# WAK-Pipe-v11.net
KiCad netlist of a schematic drawn in EAGLE
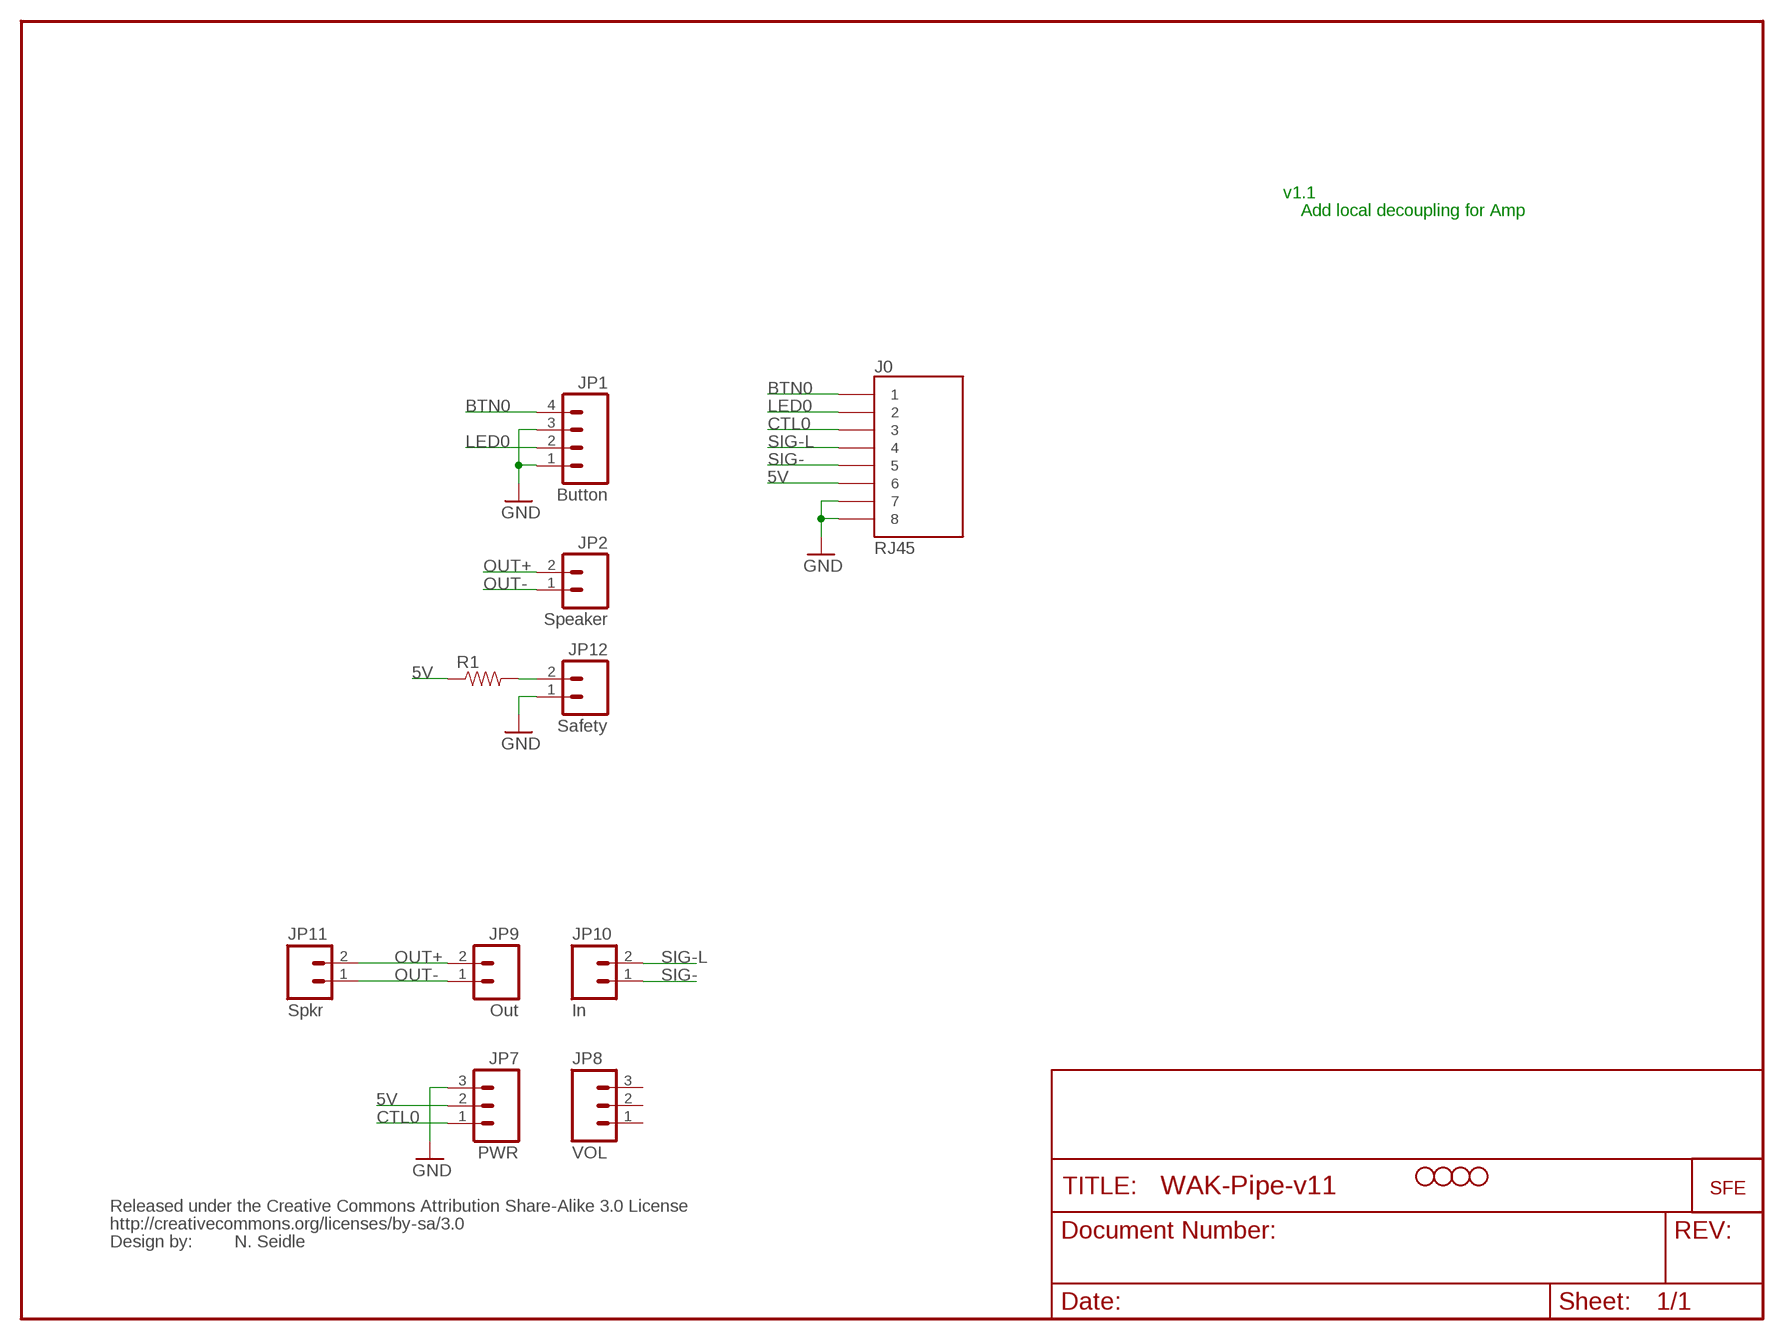
[diagram p0: schematic, sheet 1]

(export (version "E")
  (design (tool "Eeschema 10.0.6"))
  (components
    (comp (ref "J0")
      (value "RJ45")
      (footprint "eagle-import:RJ45-8")
      (libsource (lib "eagle-import") (part "RJ45-8PTH"))
    )
    (comp (ref "JP1")
      (value "Button")
      (footprint "eagle-import:JST-4-PTH")
      (libsource (lib "eagle-import") (part "M04JST-PTH"))
    )
    (comp (ref "JP2")
      (value "Speaker")
      (footprint "eagle-import:JST-2-PTH")
      (libsource (lib "eagle-import") (part "M02JST-PTH-2"))
    )
    (comp (ref "JP3")
      (value "STAND-OFF")
      (footprint "eagle-import:STAND-OFF")
      (libsource (lib "eagle-import") (part "STAND-OFF"))
    )
    (comp (ref "JP4")
      (value "STAND-OFF")
      (footprint "eagle-import:STAND-OFF")
      (libsource (lib "eagle-import") (part "STAND-OFF"))
    )
    (comp (ref "JP5")
      (value "STAND-OFF")
      (footprint "eagle-import:STAND-OFF")
      (libsource (lib "eagle-import") (part "STAND-OFF"))
    )
    (comp (ref "JP6")
      (value "STAND-OFF")
      (footprint "eagle-import:STAND-OFF")
      (libsource (lib "eagle-import") (part "STAND-OFF"))
    )
    (comp (ref "JP7")
      (value "PWR")
      (footprint "eagle-import:1X03")
      (libsource (lib "eagle-import") (part "M03PTH"))
    )
    (comp (ref "JP8")
      (value "VOL")
      (footprint "eagle-import:1X03")
      (libsource (lib "eagle-import") (part "M03PTH"))
    )
    (comp (ref "JP9")
      (value "Out")
      (footprint "eagle-import:1X02")
      (libsource (lib "eagle-import") (part "M02PTH"))
    )
    (comp (ref "JP10")
      (value "In")
      (footprint "eagle-import:1X02")
      (libsource (lib "eagle-import") (part "M02PTH"))
    )
    (comp (ref "JP11")
      (value "Spkr")
      (footprint "eagle-import:1X02")
      (libsource (lib "eagle-import") (part "M02PTH"))
    )
    (comp (ref "JP12")
      (value "Safety")
      (footprint "eagle-import:JST-2-PTH")
      (libsource (lib "eagle-import") (part "M02JST-PTH-2"))
    )
    (comp (ref "R1")
      (value "RESISTORAXIAL-0.3")
      (footprint "eagle-import:AXIAL-0.3")
      (libsource (lib "eagle-import") (part "RESISTORAXIAL-0.3"))
    )
    (comp (ref "U$1")
      (value "LOGO-SFENEW")
      (footprint "eagle-import:SFE-NEW-WEBLOGO")
      (libsource (lib "eagle-import") (part "LOGO-SFENEW"))
    )
    (comp (ref "U$2")
      (value "CREATIVE_COMMONS")
      (footprint "eagle-import:CREATIVE_COMMONS")
      (libsource (lib "eagle-import") (part "CREATIVE_COMMONS"))
    )
  )
  (nets
    (net (code "1") (name "/5V") (class "Default")
      (node (ref "J0") (pin "6") (pinfunction "6_6") (pintype "bidirectional"))
      (node (ref "JP7") (pin "2") (pinfunction "2_2") (pintype "passive"))
      (node (ref "R1") (pin "P$1") (pinfunction "1_P$1") (pintype "passive"))
    )
    (net (code "2") (name "/BTN0") (class "Default")
      (node (ref "J0") (pin "1") (pinfunction "1_1") (pintype "bidirectional"))
      (node (ref "JP1") (pin "4") (pinfunction "4_4") (pintype "passive"))
    )
    (net (code "3") (name "/CTL0") (class "Default")
      (node (ref "J0") (pin "3") (pinfunction "3_3") (pintype "bidirectional"))
      (node (ref "JP7") (pin "1") (pinfunction "1_1") (pintype "passive"))
    )
    (net (code "4") (name "/LED0") (class "Default")
      (node (ref "J0") (pin "2") (pinfunction "2_2") (pintype "bidirectional"))
      (node (ref "JP1") (pin "2") (pinfunction "2_2") (pintype "passive"))
    )
    (net (code "5") (name "/OUT+") (class "Default")
      (node (ref "JP11") (pin "2") (pinfunction "2_2") (pintype "passive"))
      (node (ref "JP2") (pin "2") (pinfunction "2_2") (pintype "passive"))
      (node (ref "JP9") (pin "2") (pinfunction "2_2") (pintype "passive"))
    )
    (net (code "6") (name "/OUT-") (class "Default")
      (node (ref "JP11") (pin "1") (pinfunction "1_1") (pintype "passive"))
      (node (ref "JP2") (pin "1") (pinfunction "1_1") (pintype "passive"))
      (node (ref "JP9") (pin "1") (pinfunction "1_1") (pintype "passive"))
    )
    (net (code "7") (name "/SIG-") (class "Default")
      (node (ref "J0") (pin "5") (pinfunction "5_5") (pintype "bidirectional"))
      (node (ref "JP10") (pin "1") (pinfunction "1_1") (pintype "passive"))
    )
    (net (code "8") (name "/SIG-L") (class "Default")
      (node (ref "J0") (pin "4") (pinfunction "4_4") (pintype "bidirectional"))
      (node (ref "JP10") (pin "2") (pinfunction "2_2") (pintype "passive"))
    )
    (net (code "9") (name "GND") (class "Default")
      (node (ref "J0") (pin "7") (pinfunction "7_7") (pintype "bidirectional"))
      (node (ref "J0") (pin "8") (pinfunction "8_8") (pintype "bidirectional"))
      (node (ref "JP1") (pin "1") (pinfunction "1_1") (pintype "passive"))
      (node (ref "JP1") (pin "3") (pinfunction "3_3") (pintype "passive"))
      (node (ref "JP12") (pin "1") (pinfunction "1_1") (pintype "passive"))
      (node (ref "JP7") (pin "3") (pinfunction "3_3") (pintype "passive"))
    )
    (net (code "10") (name "Net-(R1-2)") (class "Default")
      (node (ref "JP12") (pin "2") (pinfunction "2_2") (pintype "passive"))
      (node (ref "R1") (pin "P$2") (pinfunction "2_P$2") (pintype "passive"))
    )
    (net (code "11") (name "unconnected-(JP8-Pad1)") (class "Default")
      (node (ref "JP8") (pin "1") (pinfunction "1_1") (pintype "passive"))
    )
    (net (code "12") (name "unconnected-(JP8-Pad2)") (class "Default")
      (node (ref "JP8") (pin "2") (pinfunction "2_2") (pintype "passive"))
    )
    (net (code "13") (name "unconnected-(JP8-Pad3)") (class "Default")
      (node (ref "JP8") (pin "3") (pinfunction "3_3") (pintype "passive"))
    )
  )
)
